# Sheet.net
KiCad netlist of a schematic drawn in Altium Designer
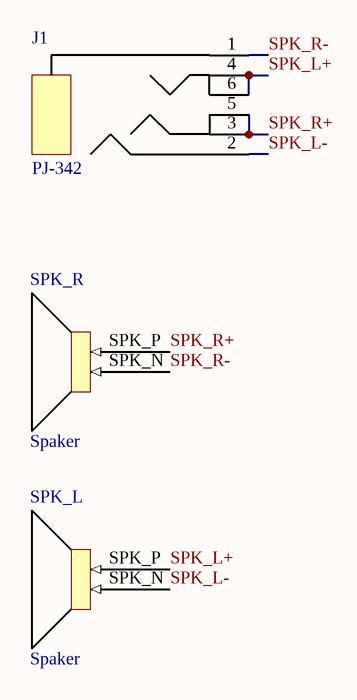
[diagram p0: Sheet.SchDoc]

(export (version "E")
  (design (tool "Eeschema 10.0.6"))
  (components
    (comp (ref "J1") (value "PJ-342") (footprint "PJ-342") (libsource (lib "SchLib") (part "PJ-342")))
    (comp (ref "SPK_L") (value "Spaker") (footprint "SPAKER") (libsource (lib "SchLib") (part "Spaker")))
    (comp (ref "SPK_R") (value "Spaker") (footprint "SPAKER") (libsource (lib "SchLib") (part "Spaker")))
  )
  (nets
    (net (code "1") (name "/SPK_L+") (class "Default")
      (node (ref "J1") (pin "4") (pinfunction "4_4") (pintype "passive"))
      (node (ref "J1") (pin "6") (pinfunction "6_6") (pintype "passive"))
      (node (ref "SPK_L") (pin "SPK_P") (pinfunction "SPK_P_SPK_P") (pintype "input"))
    )
    (net (code "2") (name "/SPK_L-") (class "Default")
      (node (ref "J1") (pin "2") (pinfunction "2_2") (pintype "passive"))
      (node (ref "SPK_L") (pin "SPK_N") (pinfunction "SPK_N_SPK_N") (pintype "input"))
    )
    (net (code "3") (name "/SPK_R+") (class "Default")
      (node (ref "J1") (pin "3") (pinfunction "3_3") (pintype "passive"))
      (node (ref "J1") (pin "5") (pinfunction "5_5") (pintype "passive"))
      (node (ref "SPK_R") (pin "SPK_P") (pinfunction "SPK_P_SPK_P") (pintype "input"))
    )
    (net (code "4") (name "/SPK_R-") (class "Default")
      (node (ref "J1") (pin "1") (pinfunction "1_1") (pintype "passive"))
      (node (ref "SPK_R") (pin "SPK_N") (pinfunction "SPK_N_SPK_N") (pintype "input"))
    )
  )
)
